# fet_switch.net
KiCad netlist of a schematic drawn in EAGLE
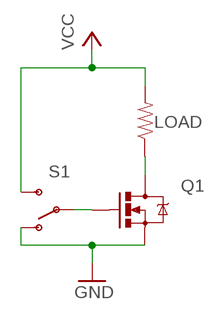
[diagram p0: schematic, sheet 1]

(export (version "E")
  (design (tool "Eeschema 10.0.6"))
  (components
    (comp (ref "LOAD")
      (value "RESISTOR0402-RES")
      (footprint "eagle-import:0402-RES")
      (libsource (lib "eagle-import") (part "RESISTOR0402-RES"))
    )
    (comp (ref "Q1")
      (value "MOSFET-NCHANNEL2N7000")
      (footprint "eagle-import:TO-92")
      (libsource (lib "eagle-import") (part "MOSFET-NCHANNEL2N7000"))
    )
    (comp (ref "S1")
      (value "SWITCH-SPDT-SMD-A")
      (footprint "eagle-import:SWITCH-SPST-SMD-A")
      (libsource (lib "eagle-import") (part "SWITCH-SPDT-SMD-A"))
    )
  )
  (nets
    (net (code "1") (name "GND") (class "Default")
      (node (ref "Q1") (pin "1") (pinfunction "S_1") (pintype "passive"))
      (node (ref "S1") (pin "1") (pinfunction "O_1") (pintype "passive"))
    )
    (net (code "2") (name "Net-(Q1-D)") (class "Default")
      (node (ref "LOAD") (pin "1") (pinfunction "1_1") (pintype "passive"))
      (node (ref "Q1") (pin "3") (pinfunction "D_3") (pintype "passive"))
    )
    (net (code "3") (name "Net-(Q1-G)") (class "Default")
      (node (ref "Q1") (pin "2") (pinfunction "G_2") (pintype "passive"))
      (node (ref "S1") (pin "2") (pinfunction "P_2") (pintype "passive"))
    )
    (net (code "4") (name "VCC") (class "Default")
      (node (ref "LOAD") (pin "2") (pinfunction "2_2") (pintype "passive"))
      (node (ref "S1") (pin "3") (pinfunction "S_3") (pintype "passive"))
    )
  )
)
